# TinyGlo.net
KiCad netlist of a schematic drawn in EAGLE
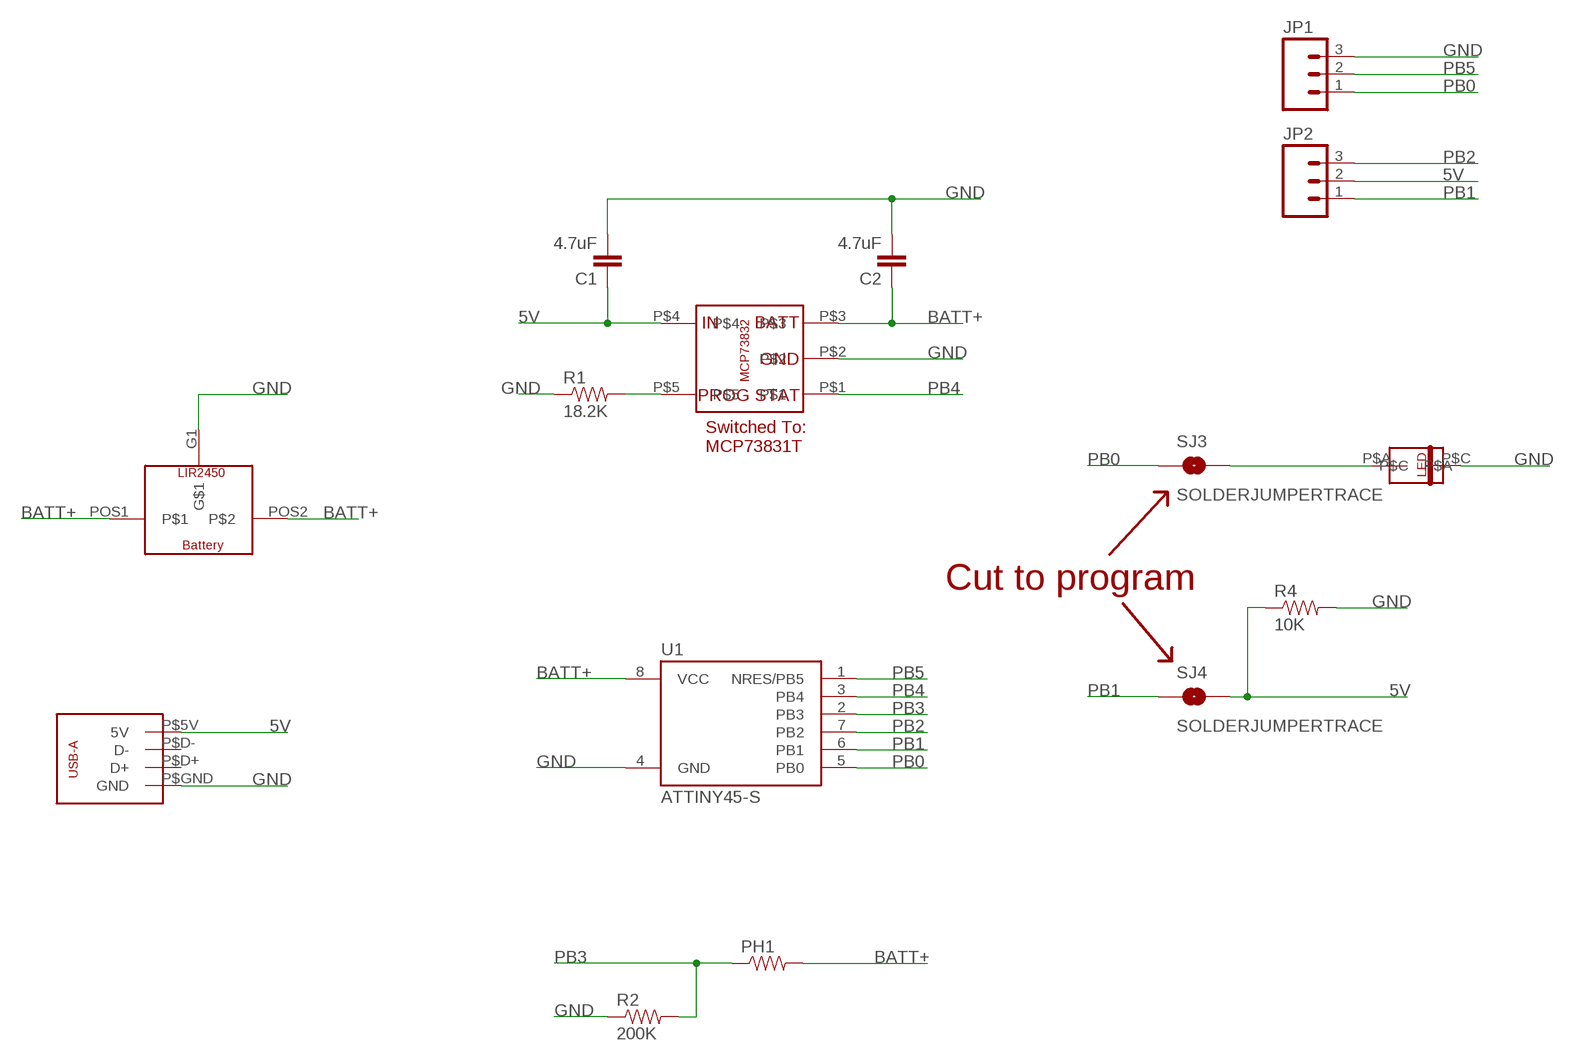
[diagram p0: schematic, sheet 1]

(export (version "E")
  (design (tool "Eeschema 10.0.6"))
  (components
    (comp (ref "C1")
      (value "4.7uF")
      (footprint "eagle-import:0603-CAP")
      (libsource (lib "eagle-import") (part "CAP0603-CAP"))
    )
    (comp (ref "C2")
      (value "4.7uF")
      (footprint "eagle-import:0603-CAP")
      (libsource (lib "eagle-import") (part "CAP0603-CAP"))
    )
    (comp (ref "JP1")
      (value "M03LOCK")
      (footprint "eagle-import:1X03_LOCK")
      (libsource (lib "eagle-import") (part "M03LOCK"))
    )
    (comp (ref "JP2")
      (value "M03LOCK")
      (footprint "eagle-import:1X03_LOCK")
      (libsource (lib "eagle-import") (part "M03LOCK"))
    )
    (comp (ref "PH1")
      (value "RESISTOR0805-RES")
      (footprint "eagle-import:0805")
      (libsource (lib "eagle-import") (part "SparkFun-Resistors_RESISTOR0805-RES"))
    )
    (comp (ref "R1")
      (value "18.2K")
      (footprint "eagle-import:0603-RES")
      (libsource (lib "eagle-import") (part "RESISTOR0603-RES"))
    )
    (comp (ref "R2")
      (value "200K")
      (footprint "eagle-import:0603-RES")
      (libsource (lib "eagle-import") (part "RESISTOR0603-RES"))
    )
    (comp (ref "R4")
      (value "10K")
      (footprint "eagle-import:0603-RES")
      (libsource (lib "eagle-import") (part "RESISTOR0603-RES"))
    )
    (comp (ref "SJ3")
      (value "SOLDERJUMPERTRACE")
      (footprint "eagle-import:SJ_2S-TRACE")
      (libsource (lib "eagle-import") (part "SOLDERJUMPERTRACE"))
    )
    (comp (ref "SJ4")
      (value "SOLDERJUMPERTRACE")
      (footprint "eagle-import:SJ_2S-TRACE")
      (libsource (lib "eagle-import") (part "SOLDERJUMPERTRACE"))
    )
    (comp (ref "U$1")
      (value "LIPOBATTCHG-MCP73832T-2DFI/OT")
      (footprint "eagle-import:LIPOBATTCHG-MCP73832T-2DFI_OT")
      (libsource (lib "eagle-import") (part "LIPOBATTCHG-MCP73832T-2DFI/OT"))
    )
    (comp (ref "U$2")
      (value "LIR2450_SMD_BATT_BK-5033")
      (footprint "eagle-import:LIR2450_SMD_BATT_BK-5033")
      (libsource (lib "eagle-import") (part "LIR2450_SMD_BATT_BK-5033"))
    )
    (comp (ref "U$3")
      (value "USB-A_PCB_TRACES")
      (footprint "eagle-import:USB-A_PCB_TRACES")
      (libsource (lib "eagle-import") (part "USB-A_PCB_TRACES"))
    )
    (comp (ref "U$4")
      (value "PLCC-2_LED")
      (footprint "eagle-import:PLCC-2_LED")
      (libsource (lib "eagle-import") (part "PLCC-2_LED"))
    )
    (comp (ref "U1")
      (value "ATTINY45-S")
      (footprint "eagle-import:SOIC8_EIAJ_208MIL")
      (libsource (lib "eagle-import") (part "ATTINY45S-"))
    )
  )
  (nets
    (net (code "1") (name "/5V") (class "Default")
      (node (ref "C1") (pin "1") (pinfunction "1_1") (pintype "passive"))
      (node (ref "JP2") (pin "2") (pinfunction "2_2") (pintype "passive"))
      (node (ref "R4") (pin "1") (pinfunction "1_1") (pintype "passive"))
      (node (ref "SJ4") (pin "2") (pinfunction "2_2") (pintype "passive"))
      (node (ref "U$1") (pin "P$4") (pinfunction "P$4_P$4") (pintype "bidirectional"))
      (node (ref "U$3") (pin "P$5V") (pinfunction "5V_P$5V") (pintype "bidirectional"))
    )
    (net (code "2") (name "/BATT+") (class "Default")
      (node (ref "C2") (pin "1") (pinfunction "1_1") (pintype "passive"))
      (node (ref "PH1") (pin "2") (pinfunction "2_2") (pintype "passive"))
      (node (ref "U$1") (pin "P$3") (pinfunction "P$3_P$3") (pintype "bidirectional"))
      (node (ref "U$2") (pin "POS1") (pinfunction "P$1_POS1") (pintype "bidirectional"))
      (node (ref "U$2") (pin "POS2") (pinfunction "P$2_POS2") (pintype "bidirectional"))
      (node (ref "U1") (pin "8") (pinfunction "VCC_8") (pintype "power_in"))
    )
    (net (code "3") (name "/GND") (class "Default")
      (node (ref "C1") (pin "2") (pinfunction "2_2") (pintype "passive"))
      (node (ref "C2") (pin "2") (pinfunction "2_2") (pintype "passive"))
      (node (ref "JP1") (pin "3") (pinfunction "3_3") (pintype "passive"))
      (node (ref "R1") (pin "1") (pinfunction "1_1") (pintype "passive"))
      (node (ref "R2") (pin "1") (pinfunction "1_1") (pintype "passive"))
      (node (ref "R4") (pin "2") (pinfunction "2_2") (pintype "passive"))
      (node (ref "U$1") (pin "P$2") (pinfunction "P$2_P$2") (pintype "bidirectional"))
      (node (ref "U$2") (pin "G1") (pinfunction "G$1_G1") (pintype "bidirectional"))
      (node (ref "U$3") (pin "P$GND") (pinfunction "GND_P$GND") (pintype "bidirectional"))
      (node (ref "U$4") (pin "P$C") (pinfunction "P$C_P$C") (pintype "bidirectional"))
      (node (ref "U1") (pin "4") (pinfunction "GND_4") (pintype "power_in"))
    )
    (net (code "4") (name "/PB0") (class "Default")
      (node (ref "JP1") (pin "1") (pinfunction "1_1") (pintype "passive"))
      (node (ref "SJ3") (pin "1") (pinfunction "1_1") (pintype "passive"))
      (node (ref "U1") (pin "5") (pinfunction "PB0_5") (pintype "bidirectional"))
    )
    (net (code "5") (name "/PB1") (class "Default")
      (node (ref "JP2") (pin "1") (pinfunction "1_1") (pintype "passive"))
      (node (ref "SJ4") (pin "1") (pinfunction "1_1") (pintype "passive"))
      (node (ref "U1") (pin "6") (pinfunction "PB1_6") (pintype "bidirectional"))
    )
    (net (code "6") (name "/PB2") (class "Default")
      (node (ref "JP2") (pin "3") (pinfunction "3_3") (pintype "passive"))
      (node (ref "U1") (pin "7") (pinfunction "PB2_7") (pintype "bidirectional"))
    )
    (net (code "7") (name "/PB3") (class "Default")
      (node (ref "PH1") (pin "1") (pinfunction "1_1") (pintype "passive"))
      (node (ref "R2") (pin "2") (pinfunction "2_2") (pintype "passive"))
      (node (ref "U1") (pin "2") (pinfunction "PB3_2") (pintype "bidirectional"))
    )
    (net (code "8") (name "/PB4") (class "Default")
      (node (ref "U$1") (pin "P$1") (pinfunction "P$1_P$1") (pintype "bidirectional"))
      (node (ref "U1") (pin "3") (pinfunction "PB4_3") (pintype "bidirectional"))
    )
    (net (code "9") (name "/PB5") (class "Default")
      (node (ref "JP1") (pin "2") (pinfunction "2_2") (pintype "passive"))
      (node (ref "U1") (pin "1") (pinfunction "NRES/PB5_1") (pintype "bidirectional"))
    )
    (net (code "10") (name "Net-(R1-Pad2)") (class "Default")
      (node (ref "R1") (pin "2") (pinfunction "2_2") (pintype "passive"))
      (node (ref "U$1") (pin "P$5") (pinfunction "P$5_P$5") (pintype "bidirectional"))
    )
    (net (code "11") (name "Net-(SJ3-Pad2)") (class "Default")
      (node (ref "SJ3") (pin "2") (pinfunction "2_2") (pintype "passive"))
      (node (ref "U$4") (pin "P$A") (pinfunction "P$A_P$A") (pintype "bidirectional"))
    )
    (net (code "12") (name "unconnected-(U$3-D+-PadP$D+)") (class "Default")
      (node (ref "U$3") (pin "P$D+") (pinfunction "D+_P$D+") (pintype "bidirectional"))
    )
    (net (code "13") (name "unconnected-(U$3-D--PadP$D-)") (class "Default")
      (node (ref "U$3") (pin "P$D-") (pinfunction "D-_P$D-") (pintype "bidirectional"))
    )
  )
)
